# Grove-loudness_sensor.net
KiCad netlist of a schematic drawn in EAGLE
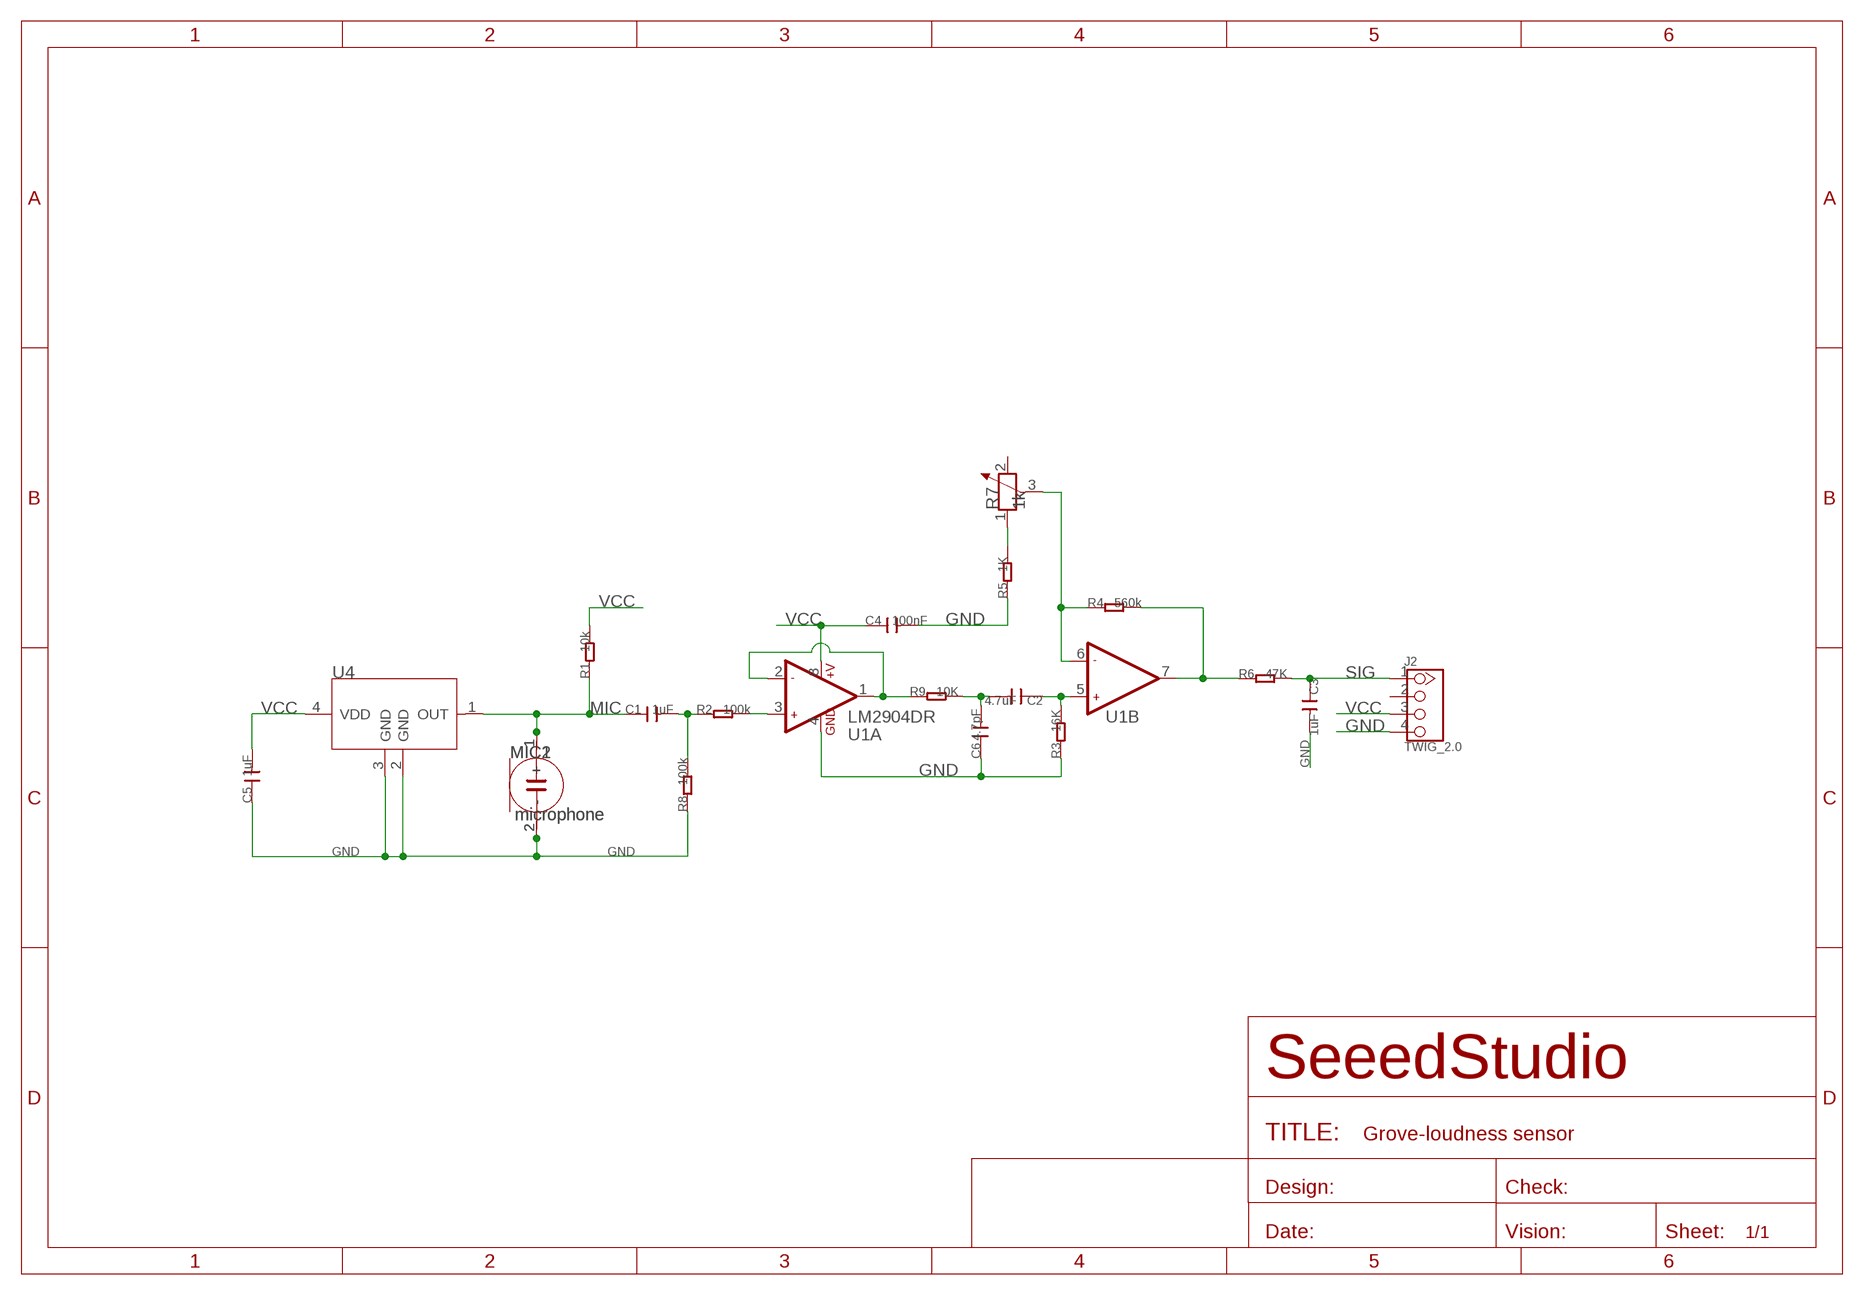
[diagram p0: schematic, sheet 1]

(export (version "E")
  (design (tool "Eeschema 10.0.6"))
  (components
    (comp (ref "C1")
      (value "1uF")
      (footprint "eagle-import:C0603")
      (libsource (lib "eagle-import") (part "C-0603"))
    )
    (comp (ref "C2")
      (value "4.7uF")
      (footprint "eagle-import:C0805")
      (libsource (lib "eagle-import") (part "C-0805"))
    )
    (comp (ref "C3")
      (value "1uF")
      (footprint "eagle-import:C0603")
      (libsource (lib "eagle-import") (part "C-0603"))
    )
    (comp (ref "C4")
      (value "100nF")
      (footprint "eagle-import:C0603")
      (libsource (lib "eagle-import") (part "C-0603"))
    )
    (comp (ref "C5")
      (value "1uF")
      (footprint "eagle-import:C0603")
      (libsource (lib "eagle-import") (part "C-0603"))
    )
    (comp (ref "C6")
      (value "4.7pF")
      (footprint "eagle-import:C0603")
      (libsource (lib "eagle-import") (part "C-0603"))
    )
    (comp (ref "J2")
      (value "TWIG_2.0")
      (footprint "eagle-import:2.0_1X4")
      (libsource (lib "eagle-import") (part "TWIG_2.0"))
    )
    (comp (ref "MIC1")
      (value "microphone")
      (footprint "eagle-import:2P-D8.9MM")
      (libsource (lib "eagle-import") (part "MICROPHONE"))
    )
    (comp (ref "MIC2")
      (value "microphone")
      (footprint "eagle-import:2P-D8.9MM")
      (libsource (lib "eagle-import") (part "MICROPHONE"))
    )
    (comp (ref "R1")
      (value "10k")
      (footprint "eagle-import:R0603")
      (libsource (lib "eagle-import") (part "R-0603"))
    )
    (comp (ref "R2")
      (value "100k")
      (footprint "eagle-import:R0603")
      (libsource (lib "eagle-import") (part "R-0603"))
    )
    (comp (ref "R3")
      (value "16K")
      (footprint "eagle-import:R0603")
      (libsource (lib "eagle-import") (part "R-0603"))
    )
    (comp (ref "R4")
      (value "560k")
      (footprint "eagle-import:R0603")
      (libsource (lib "eagle-import") (part "R-0603"))
    )
    (comp (ref "R5")
      (value "1K")
      (footprint "eagle-import:R0603")
      (libsource (lib "eagle-import") (part "R-0603"))
    )
    (comp (ref "R6")
      (value "47K")
      (footprint "eagle-import:R0603")
      (libsource (lib "eagle-import") (part "R-0603"))
    )
    (comp (ref "R7")
      (value "1k")
      (footprint "eagle-import:3P-SQUA-7X6.8")
      (libsource (lib "eagle-import") (part "R-POTENTIOMETER'3362'"))
    )
    (comp (ref "R8")
      (value "100k")
      (footprint "eagle-import:R0603")
      (libsource (lib "eagle-import") (part "R-0603"))
    )
    (comp (ref "R9")
      (value "10K")
      (footprint "eagle-import:R0603")
      (libsource (lib "eagle-import") (part "R-0603"))
    )
    (comp (ref "U1")
      (value "LM2904DR")
      (footprint "eagle-import:SO08")
      (libsource (lib "eagle-import") (part "LMV358D"))
    )
    (comp (ref "U4")
      (value "SENSOR-MULPS4CX")
      (footprint "eagle-import:4P-SMD-2.95X3.76X1.1H")
      (libsource (lib "eagle-import") (part "SENSOR-MULPS4CX"))
    )
  )
  (nets
    (net (code "1") (name "/GND") (class "Default")
      (node (ref "C3") (pin "2") (pinfunction "2_2") (pintype "passive"))
      (node (ref "C4") (pin "2") (pinfunction "2_2") (pintype "passive"))
      (node (ref "C5") (pin "1") (pinfunction "1_1") (pintype "passive"))
      (node (ref "C6") (pin "1") (pinfunction "1_1") (pintype "passive"))
      (node (ref "J2") (pin "4") (pinfunction "4_4") (pintype "bidirectional"))
      (node (ref "MIC1") (pin "2") (pinfunction "-_2") (pintype "bidirectional"))
      (node (ref "MIC2") (pin "2") (pinfunction "-_2") (pintype "bidirectional"))
      (node (ref "R3") (pin "1") (pinfunction "1_1") (pintype "passive"))
      (node (ref "R5") (pin "1") (pinfunction "1_1") (pintype "passive"))
      (node (ref "R8") (pin "1") (pinfunction "1_1") (pintype "passive"))
      (node (ref "U1") (pin "4") (pinfunction "GND_4") (pintype "power_in"))
      (node (ref "U4") (pin "2") (pinfunction "GND_2") (pintype "bidirectional"))
      (node (ref "U4") (pin "3") (pinfunction "GND_3") (pintype "bidirectional"))
    )
    (net (code "2") (name "/MIC") (class "Default")
      (node (ref "C1") (pin "1") (pinfunction "1_1") (pintype "passive"))
      (node (ref "MIC1") (pin "1") (pinfunction "+_1") (pintype "bidirectional"))
      (node (ref "MIC2") (pin "1") (pinfunction "+_1") (pintype "bidirectional"))
      (node (ref "R1") (pin "1") (pinfunction "1_1") (pintype "passive"))
      (node (ref "U4") (pin "1") (pinfunction "OUT_1") (pintype "bidirectional"))
    )
    (net (code "3") (name "/SIG") (class "Default")
      (node (ref "C3") (pin "1") (pinfunction "1_1") (pintype "passive"))
      (node (ref "J2") (pin "1") (pinfunction "1_1") (pintype "bidirectional"))
      (node (ref "R6") (pin "2") (pinfunction "2_2") (pintype "passive"))
    )
    (net (code "4") (name "/VCC") (class "Default")
      (node (ref "C4") (pin "1") (pinfunction "1_1") (pintype "passive"))
      (node (ref "C5") (pin "2") (pinfunction "2_2") (pintype "passive"))
      (node (ref "J2") (pin "3") (pinfunction "3_3") (pintype "bidirectional"))
      (node (ref "R1") (pin "2") (pinfunction "2_2") (pintype "passive"))
      (node (ref "U1") (pin "8") (pinfunction "+V_8") (pintype "power_in"))
      (node (ref "U4") (pin "4") (pinfunction "VDD_4") (pintype "bidirectional"))
    )
    (net (code "5") (name "Net-(C1-Pad2)") (class "Default")
      (node (ref "C1") (pin "2") (pinfunction "2_2") (pintype "passive"))
      (node (ref "R2") (pin "1") (pinfunction "1_1") (pintype "passive"))
      (node (ref "R8") (pin "2") (pinfunction "2_2") (pintype "passive"))
    )
    (net (code "6") (name "Net-(C2-Pad2)") (class "Default")
      (node (ref "C2") (pin "2") (pinfunction "2_2") (pintype "passive"))
      (node (ref "C6") (pin "2") (pinfunction "2_2") (pintype "passive"))
      (node (ref "R9") (pin "2") (pinfunction "2_2") (pintype "passive"))
    )
    (net (code "7") (name "Net-(R5-Pad2)") (class "Default")
      (node (ref "R5") (pin "2") (pinfunction "2_2") (pintype "passive"))
      (node (ref "R7") (pin "1") (pinfunction "1_1") (pintype "passive"))
    )
    (net (code "8") (name "Net-(U1A-+IN1)") (class "Default")
      (node (ref "R2") (pin "2") (pinfunction "2_2") (pintype "passive"))
      (node (ref "U1") (pin "3") (pinfunction "+IN1_3") (pintype "input"))
    )
    (net (code "9") (name "Net-(U1A--IN1)") (class "Default")
      (node (ref "R9") (pin "1") (pinfunction "1_1") (pintype "passive"))
      (node (ref "U1") (pin "1") (pinfunction "OUT1_1") (pintype "output"))
      (node (ref "U1") (pin "2") (pinfunction "-IN1_2") (pintype "input"))
    )
    (net (code "10") (name "Net-(U1B-+IN2)") (class "Default")
      (node (ref "C2") (pin "1") (pinfunction "1_1") (pintype "passive"))
      (node (ref "R3") (pin "2") (pinfunction "2_2") (pintype "passive"))
      (node (ref "U1") (pin "5") (pinfunction "+IN2_5") (pintype "input"))
    )
    (net (code "11") (name "Net-(U1B--IN2)") (class "Default")
      (node (ref "R4") (pin "1") (pinfunction "1_1") (pintype "passive"))
      (node (ref "R7") (pin "3") (pinfunction "3_3") (pintype "passive"))
      (node (ref "U1") (pin "6") (pinfunction "-IN2_6") (pintype "input"))
    )
    (net (code "12") (name "Net-(U1B-OUT2)") (class "Default")
      (node (ref "R4") (pin "2") (pinfunction "2_2") (pintype "passive"))
      (node (ref "R6") (pin "1") (pinfunction "1_1") (pintype "passive"))
      (node (ref "U1") (pin "7") (pinfunction "OUT2_7") (pintype "output"))
    )
    (net (code "13") (name "unconnected-(J2-Pad2)") (class "Default")
      (node (ref "J2") (pin "2") (pinfunction "2_2") (pintype "bidirectional"))
    )
    (net (code "14") (name "unconnected-(R7-Pad2)") (class "Default")
      (node (ref "R7") (pin "2") (pinfunction "2_2") (pintype "passive"))
    )
  )
)
